# stm32devboard_f401ccu6.net
KiCad netlist of a schematic drawn in EasyEDA Pro
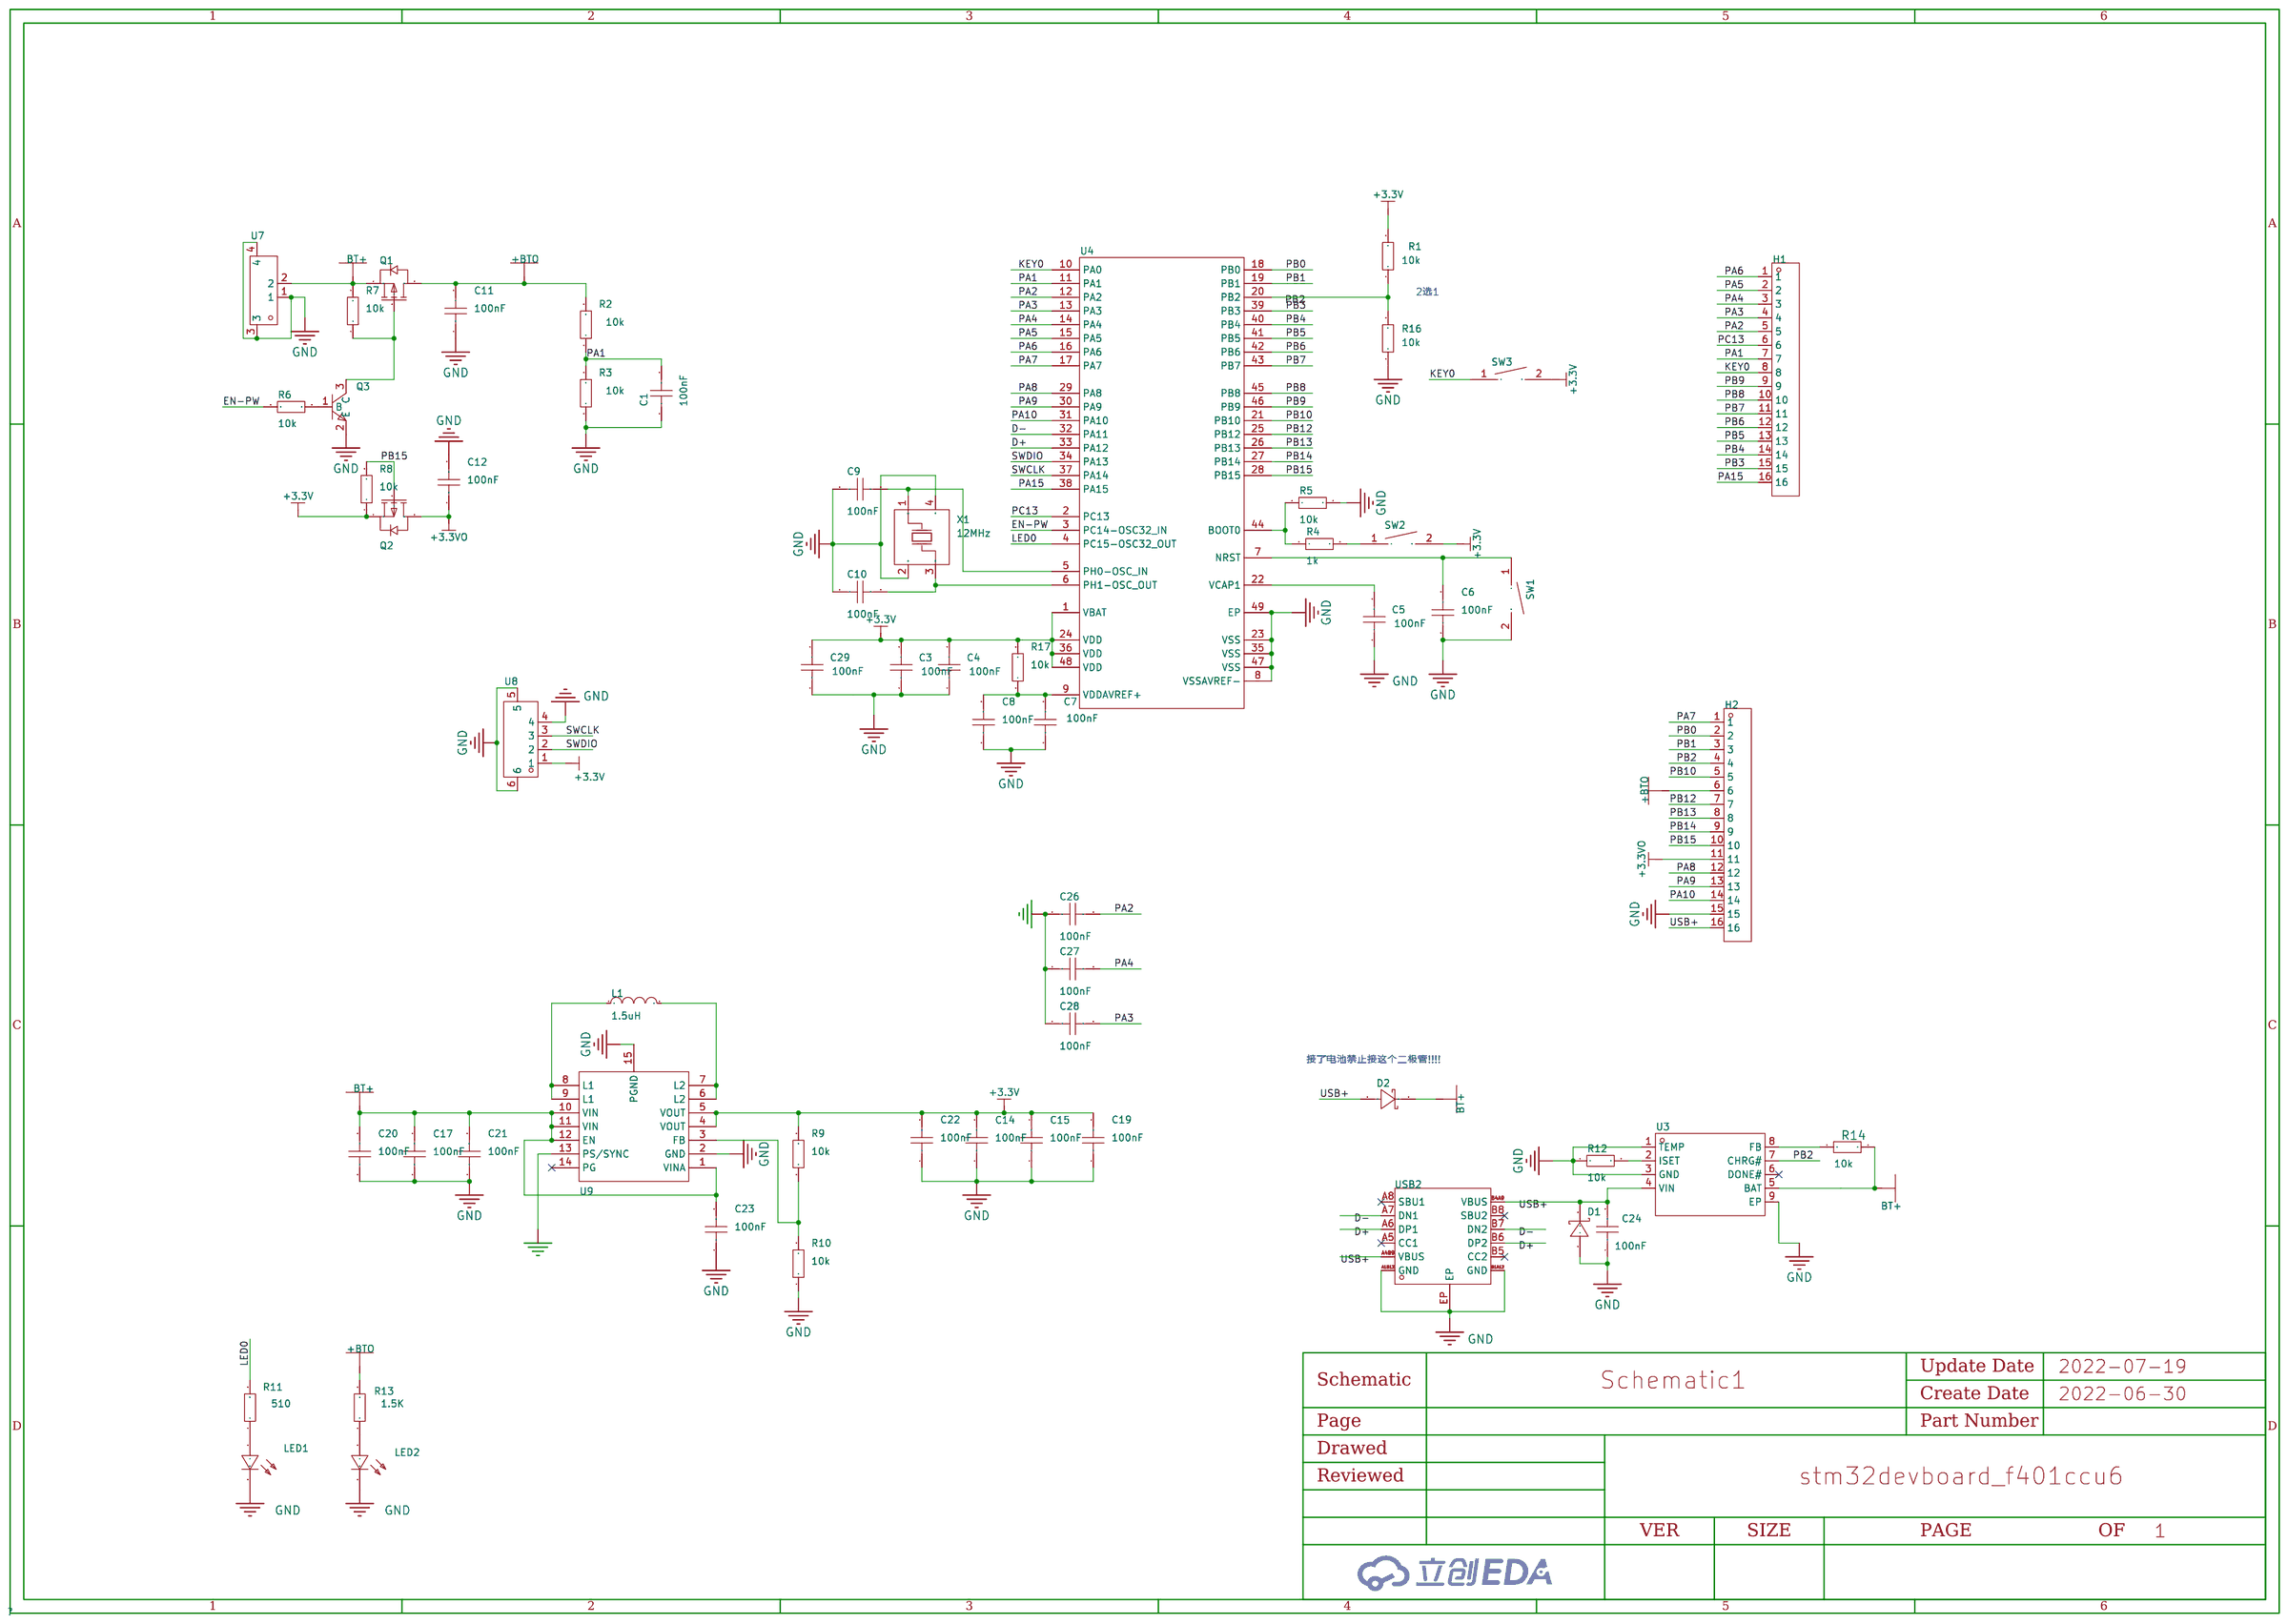
[diagram p0: schematic sheet]

(export (version "E")
  (design (tool "Eeschema 10.0.6"))
  (components
    (comp (ref "C1")
      (value "100nF")
      (footprint "easyedapro:C0402")
      (description "容值:100nF;精度:±10%;额定电压:25V;温度系数:X7R;")
      (fields (field (name "Manufacturer Part") "FN15X104K250PNG") (field (name "Manufacturer") "PSA(信昌电陶)"))
      (libsource (lib "easyedapro") (part "FN15X104K250PNG"))
    )
    (comp (ref "C3")
      (value "100nF")
      (footprint "easyedapro:C0603")
      (description "容值:100nF;精度:±10%;额定电压:50V;温度系数:X7R;")
      (fields
        (field (name "Manufacturer Part") "CC0603KRX7R9BB104")
        (field (name "Manufacturer") "YAGEO(国巨)")
      )
      (libsource (lib "easyedapro") (part "CC0603KRX7R9BB104"))
    )
    (comp (ref "C4")
      (value "100nF")
      (footprint "easyedapro:C0603")
      (description "容值:100nF;精度:±10%;额定电压:50V;温度系数:X7R;")
      (fields
        (field (name "Manufacturer Part") "CC0603KRX7R9BB104")
        (field (name "Manufacturer") "YAGEO(国巨)")
      )
      (libsource (lib "easyedapro") (part "CC0603KRX7R9BB104"))
    )
    (comp (ref "C5")
      (value "100nF")
      (footprint "easyedapro:C0603")
      (description "容值:100nF;精度:±10%;额定电压:50V;温度系数:X7R;")
      (fields
        (field (name "Manufacturer Part") "CC0603KRX7R9BB104")
        (field (name "Manufacturer") "YAGEO(国巨)")
      )
      (libsource (lib "easyedapro") (part "CC0603KRX7R9BB104"))
    )
    (comp (ref "C6")
      (value "100nF")
      (footprint "easyedapro:C0603")
      (description "容值:100nF;精度:±10%;额定电压:50V;温度系数:X7R;")
      (fields
        (field (name "Manufacturer Part") "CC0603KRX7R9BB104")
        (field (name "Manufacturer") "YAGEO(国巨)")
      )
      (libsource (lib "easyedapro") (part "CC0603KRX7R9BB104"))
    )
    (comp (ref "C7")
      (value "100nF")
      (footprint "easyedapro:C0603")
      (description "容值:100nF;精度:±10%;额定电压:50V;温度系数:X7R;")
      (fields
        (field (name "Manufacturer Part") "CC0603KRX7R9BB104")
        (field (name "Manufacturer") "YAGEO(国巨)")
      )
      (libsource (lib "easyedapro") (part "CC0603KRX7R9BB104"))
    )
    (comp (ref "C8")
      (value "100nF")
      (footprint "easyedapro:C0603")
      (description "容值:100nF;精度:±10%;额定电压:50V;温度系数:X7R;")
      (fields
        (field (name "Manufacturer Part") "CC0603KRX7R9BB104")
        (field (name "Manufacturer") "YAGEO(国巨)")
      )
      (libsource (lib "easyedapro") (part "CC0603KRX7R9BB104"))
    )
    (comp (ref "C9")
      (value "100nF")
      (footprint "easyedapro:C0603")
      (description "容值:100nF;精度:±10%;额定电压:50V;温度系数:X7R;")
      (fields
        (field (name "Manufacturer Part") "CC0603KRX7R9BB104")
        (field (name "Manufacturer") "YAGEO(国巨)")
      )
      (libsource (lib "easyedapro") (part "CC0603KRX7R9BB104"))
    )
    (comp (ref "C10")
      (value "100nF")
      (footprint "easyedapro:C0603")
      (description "容值:100nF;精度:±10%;额定电压:50V;温度系数:X7R;")
      (fields
        (field (name "Manufacturer Part") "CC0603KRX7R9BB104")
        (field (name "Manufacturer") "YAGEO(国巨)")
      )
      (libsource (lib "easyedapro") (part "CC0603KRX7R9BB104"))
    )
    (comp (ref "C11")
      (value "100nF")
      (footprint "easyedapro:C0603")
      (description "容值:100nF;精度:±10%;额定电压:50V;温度系数:X7R;")
      (fields
        (field (name "Manufacturer Part") "CC0603KRX7R9BB104")
        (field (name "Manufacturer") "YAGEO(国巨)")
      )
      (libsource (lib "easyedapro") (part "CC0603KRX7R9BB104"))
    )
    (comp (ref "C12")
      (value "100nF")
      (footprint "easyedapro:C0603")
      (description "容值:100nF;精度:±10%;额定电压:50V;温度系数:X7R;")
      (fields
        (field (name "Manufacturer Part") "CC0603KRX7R9BB104")
        (field (name "Manufacturer") "YAGEO(国巨)")
      )
      (libsource (lib "easyedapro") (part "CC0603KRX7R9BB104"))
    )
    (comp (ref "C14")
      (value "100nF")
      (footprint "easyedapro:C0603")
      (description "容值:100nF;精度:±10%;额定电压:50V;温度系数:X7R;")
      (fields
        (field (name "Manufacturer Part") "CC0603KRX7R9BB104")
        (field (name "Manufacturer") "YAGEO(国巨)")
      )
      (libsource (lib "easyedapro") (part "CC0603KRX7R9BB104"))
    )
    (comp (ref "C15")
      (value "100nF")
      (footprint "easyedapro:C0603")
      (description "容值:100nF;精度:±10%;额定电压:50V;温度系数:X7R;")
      (fields
        (field (name "Manufacturer Part") "CC0603KRX7R9BB104")
        (field (name "Manufacturer") "YAGEO(国巨)")
      )
      (libsource (lib "easyedapro") (part "CC0603KRX7R9BB104"))
    )
    (comp (ref "C17")
      (value "100nF")
      (footprint "easyedapro:C0603")
      (description "容值:100nF;精度:±10%;额定电压:50V;温度系数:X7R;")
      (fields
        (field (name "Manufacturer Part") "CC0603KRX7R9BB104")
        (field (name "Manufacturer") "YAGEO(国巨)")
      )
      (libsource (lib "easyedapro") (part "CC0603KRX7R9BB104"))
    )
    (comp (ref "C19")
      (value "100nF")
      (footprint "easyedapro:C0603")
      (description "容值:100nF;精度:±10%;额定电压:50V;温度系数:X7R;")
      (fields
        (field (name "Manufacturer Part") "CC0603KRX7R9BB104")
        (field (name "Manufacturer") "YAGEO(国巨)")
      )
      (libsource (lib "easyedapro") (part "CC0603KRX7R9BB104"))
    )
    (comp (ref "C20")
      (value "100nF")
      (footprint "easyedapro:C0603")
      (description "容值:100nF;精度:±10%;额定电压:50V;温度系数:X7R;")
      (fields
        (field (name "Manufacturer Part") "CC0603KRX7R9BB104")
        (field (name "Manufacturer") "YAGEO(国巨)")
      )
      (libsource (lib "easyedapro") (part "CC0603KRX7R9BB104"))
    )
    (comp (ref "C21")
      (value "100nF")
      (footprint "easyedapro:C0402")
      (description "容值:100nF;精度:±10%;额定电压:25V;温度系数:X7R;")
      (fields (field (name "Manufacturer Part") "FN15X104K250PNG") (field (name "Manufacturer") "PSA(信昌电陶)"))
      (libsource (lib "easyedapro") (part "FN15X104K250PNG"))
    )
    (comp (ref "C22")
      (value "100nF")
      (footprint "easyedapro:C0402")
      (description "容值:100nF;精度:±10%;额定电压:25V;温度系数:X7R;")
      (fields (field (name "Manufacturer Part") "FN15X104K250PNG") (field (name "Manufacturer") "PSA(信昌电陶)"))
      (libsource (lib "easyedapro") (part "FN15X104K250PNG"))
    )
    (comp (ref "C23")
      (value "100nF")
      (footprint "easyedapro:C0603")
      (description "容值:100nF;精度:±10%;额定电压:50V;温度系数:X7R;")
      (fields
        (field (name "Manufacturer Part") "CC0603KRX7R9BB104")
        (field (name "Manufacturer") "YAGEO(国巨)")
      )
      (libsource (lib "easyedapro") (part "CC0603KRX7R9BB104"))
    )
    (comp (ref "C24")
      (value "100nF")
      (footprint "easyedapro:C0603")
      (description "容值:100nF;精度:±10%;额定电压:50V;温度系数:X7R;")
      (fields
        (field (name "Manufacturer Part") "CC0603KRX7R9BB104")
        (field (name "Manufacturer") "YAGEO(国巨)")
      )
      (libsource (lib "easyedapro") (part "CC0603KRX7R9BB104"))
    )
    (comp (ref "C26")
      (value "100nF")
      (footprint "easyedapro:C0402")
      (description "容值:100nF;精度:±10%;额定电压:25V;温度系数:X7R;")
      (fields (field (name "Manufacturer Part") "FN15X104K250PNG") (field (name "Manufacturer") "PSA(信昌电陶)"))
      (libsource (lib "easyedapro") (part "FN15X104K250PNG"))
    )
    (comp (ref "C27")
      (value "100nF")
      (footprint "easyedapro:C0402")
      (description "容值:100nF;精度:±10%;额定电压:25V;温度系数:X7R;")
      (fields (field (name "Manufacturer Part") "FN15X104K250PNG") (field (name "Manufacturer") "PSA(信昌电陶)"))
      (libsource (lib "easyedapro") (part "FN15X104K250PNG"))
    )
    (comp (ref "C28")
      (value "100nF")
      (footprint "easyedapro:C0402")
      (description "容值:100nF;精度:±10%;额定电压:25V;温度系数:X7R;")
      (fields (field (name "Manufacturer Part") "FN15X104K250PNG") (field (name "Manufacturer") "PSA(信昌电陶)"))
      (libsource (lib "easyedapro") (part "FN15X104K250PNG"))
    )
    (comp (ref "C29")
      (value "100nF")
      (footprint "easyedapro:C0402")
      (description "容值:100nF;精度:±10%;额定电压:25V;温度系数:X7R;")
      (fields (field (name "Manufacturer Part") "FN15X104K250PNG") (field (name "Manufacturer") "PSA(信昌电陶)"))
      (libsource (lib "easyedapro") (part "FN15X104K250PNG"))
    )
    (comp (ref "D1")
      (value "~")
      (footprint "easyedapro:SOD-123FL_L2.6-W1.6-LS3.4-R-FD")
      (description "极性:单向;反向截止电压(Vrwm):5V;击穿电压(最小值):6.4V;峰值脉冲电流(Ipp)@10/1000s:21.7A;最大钳位电压:9.4V;")
      (fields (field (name "Manufacturer Part") "SMFJ5.0A") (field (name "Manufacturer") "BORN伯恩半导体"))
      (libsource (lib "easyedapro") (part "SMFJ5.0A_C151893"))
    )
    (comp (ref "D2")
      (value "~")
      (footprint "easyedapro:SOD-323_L1.6-W1.3-LS2.7-RD")
      (description "二极管配置:独立式;直流反向耐压(Vr):40V;平均整流电流(Io):350mA;正向压降(Vf):600mV@200mA;反向电流(Ir):5A@30V;")
      (fields (field (name "Manufacturer Part") "1N5819WS S4") (field (name "Manufacturer") "JSMSEMI(杰盛微)"))
      (libsource (lib "easyedapro") (part "1N5819WS S4"))
    )
    (comp (ref "H1")
      (value "~")
      (footprint "easyedapro:HDR-TH_16P-P2.54-V-M")
      (description "2.54mm 圆孔排针,单排,180度,塑高3.0mm,塑宽2.54mm,D4.3mm,L=12.20mm,PPS料,镀金,16P")
      (fields
        (field (name "Manufacturer Part") "X5511WV-16-C396D43-1220")
        (field (name "Manufacturer") "XKB Connectivity(中国星坤)")
      )
      (libsource (lib "easyedapro") (part "X5511WV-16-C396D43-1220"))
    )
    (comp (ref "H2")
      (value "~")
      (footprint "easyedapro:HDR-TH_16P-P2.54-V-M")
      (description "2.54mm 圆孔排针,单排,180度,塑高3.0mm,塑宽2.54mm,D4.3mm,L=12.20mm,PPS料,镀金,16P")
      (fields
        (field (name "Manufacturer Part") "X5511WV-16-C396D43-1220")
        (field (name "Manufacturer") "XKB Connectivity(中国星坤)")
      )
      (libsource (lib "easyedapro") (part "X5511WV-16-C396D43-1220"))
    )
    (comp (ref "L1")
      (value "1.5uH")
      (footprint "easyedapro:IND-SMD_L4.0-W4.0_FNR40XXS")
      (description "电感值:1.5uH;精度:±20%;额定电流:3.34A;直流电阻(DCR):26m;")
      (fields (field (name "Manufacturer Part") "FNR4030S1R5MT") (field (name "Manufacturer") "cjiang(长江微电)"))
      (libsource (lib "easyedapro") (part "FNR4030S1R5MT"))
    )
    (comp (ref "LED1")
      (value "~")
      (footprint "easyedapro:LED0603-R-RD")
      (description "照明颜色:翠绿;色温 - CCT（K）:-;主波长/色坐标:520~535nm;")
      (fields
        (field (name "Manufacturer Part") "19-217/GHC-YR1S2/3T")
        (field (name "Manufacturer") "EVERLIGHT(台湾亿光)")
      )
      (libsource (lib "easyedapro") (part "19-217/GHC-YR1S2/3T"))
    )
    (comp (ref "LED2")
      (value "~")
      (footprint "easyedapro:LED0603-R-RD")
      (description "照明颜色:翠绿;色温 - CCT（K）:-;主波长/色坐标:520~535nm;")
      (fields
        (field (name "Manufacturer Part") "19-217/GHC-YR1S2/3T")
        (field (name "Manufacturer") "EVERLIGHT(台湾亿光)")
      )
      (libsource (lib "easyedapro") (part "19-217/GHC-YR1S2/3T"))
    )
    (comp (ref "Q1")
      (value "~")
      (footprint "easyedapro:SOT-23-3_L2.9-W1.3-P1.90-LS2.4-TR")
      (fields (field (name "Manufacturer Part") "AP2301B") (field (name "Manufacturer") "ALLPOWER(铨力)"))
      (libsource (lib "easyedapro") (part "AP2301B"))
    )
    (comp (ref "Q2")
      (value "~")
      (footprint "easyedapro:SOT-23-3_L2.9-W1.3-P1.90-LS2.4-TR")
      (fields (field (name "Manufacturer Part") "AP2301B") (field (name "Manufacturer") "ALLPOWER(铨力)"))
      (libsource (lib "easyedapro") (part "AP2301B"))
    )
    (comp (ref "Q3")
      (value "~")
      (footprint "easyedapro:SOT-23-3_L2.9-W1.3-P1.90-LS2.4-BR")
      (fields (field (name "Manufacturer Part") "S8050 J3Y") (field (name "Manufacturer") "FOSAN(富信)"))
      (libsource (lib "easyedapro") (part "S8050_C2926165"))
    )
    (comp (ref "R1")
      (value "10k")
      (footprint "easyedapro:R0603")
      (description "电阻类型:薄膜电阻;阻值:10k;精度:±0.1%;功率:100mW;温度系数:±25ppm/;最大工作电压:75V;工作温度范围:-55~+155;")
      (fields
        (field (name "Manufacturer Part") "TR0603B10K0P0525Z")
        (field (name "Manufacturer") "EVER OHMS(天二科技)")
      )
      (libsource (lib "easyedapro") (part "R_0603_EU"))
    )
    (comp (ref "R2")
      (value "10k")
      (footprint "easyedapro:R0603")
      (description "电阻类型:薄膜电阻;阻值:10k;精度:±0.1%;功率:100mW;温度系数:±25ppm/;最大工作电压:75V;工作温度范围:-55~+155;")
      (fields
        (field (name "Manufacturer Part") "TR0603B10K0P0525Z")
        (field (name "Manufacturer") "EVER OHMS(天二科技)")
      )
      (libsource (lib "easyedapro") (part "R_0603_EU"))
    )
    (comp (ref "R3")
      (value "10k")
      (footprint "easyedapro:R0603")
      (description "电阻类型:薄膜电阻;阻值:10k;精度:±0.1%;功率:100mW;温度系数:±25ppm/;最大工作电压:75V;工作温度范围:-55~+155;")
      (fields
        (field (name "Manufacturer Part") "TR0603B10K0P0525Z")
        (field (name "Manufacturer") "EVER OHMS(天二科技)")
      )
      (libsource (lib "easyedapro") (part "R_0603_EU"))
    )
    (comp (ref "R4")
      (value "1k")
      (footprint "easyedapro:R0603")
      (description "电阻类型:薄膜电阻;阻值:10k;精度:±0.1%;功率:100mW;温度系数:±25ppm/;最大工作电压:75V;工作温度范围:-55~+155;")
      (fields
        (field (name "Manufacturer Part") "TR0603B10K0P0525Z")
        (field (name "Manufacturer") "EVER OHMS(天二科技)")
      )
      (libsource (lib "easyedapro") (part "R_0603_EU"))
    )
    (comp (ref "R5")
      (value "10k")
      (footprint "easyedapro:R0603")
      (description "电阻类型:薄膜电阻;阻值:10k;精度:±0.1%;功率:100mW;温度系数:±25ppm/;最大工作电压:75V;工作温度范围:-55~+155;")
      (fields
        (field (name "Manufacturer Part") "TR0603B10K0P0525Z")
        (field (name "Manufacturer") "EVER OHMS(天二科技)")
      )
      (libsource (lib "easyedapro") (part "R_0603_EU"))
    )
    (comp (ref "R6")
      (value "10k")
      (footprint "easyedapro:R0603")
      (description "电阻类型:薄膜电阻;阻值:10k;精度:±0.1%;功率:100mW;温度系数:±25ppm/;最大工作电压:75V;工作温度范围:-55~+155;")
      (fields
        (field (name "Manufacturer Part") "TR0603B10K0P0525Z")
        (field (name "Manufacturer") "EVER OHMS(天二科技)")
      )
      (libsource (lib "easyedapro") (part "R_0603_EU"))
    )
    (comp (ref "R7")
      (value "10k")
      (footprint "easyedapro:R0603")
      (description "电阻类型:薄膜电阻;阻值:10k;精度:±0.1%;功率:100mW;温度系数:±25ppm/;最大工作电压:75V;工作温度范围:-55~+155;")
      (fields
        (field (name "Manufacturer Part") "TR0603B10K0P0525Z")
        (field (name "Manufacturer") "EVER OHMS(天二科技)")
      )
      (libsource (lib "easyedapro") (part "R_0603_EU"))
    )
    (comp (ref "R8")
      (value "10k")
      (footprint "easyedapro:R0603")
      (description "电阻类型:薄膜电阻;阻值:10k;精度:±0.1%;功率:100mW;温度系数:±25ppm/;最大工作电压:75V;工作温度范围:-55~+155;")
      (fields
        (field (name "Manufacturer Part") "TR0603B10K0P0525Z")
        (field (name "Manufacturer") "EVER OHMS(天二科技)")
      )
      (libsource (lib "easyedapro") (part "R_0603_EU"))
    )
    (comp (ref "R9")
      (value "10k")
      (footprint "easyedapro:R0603")
      (description "电阻类型:薄膜电阻;阻值:10k;精度:±0.1%;功率:100mW;温度系数:±25ppm/;最大工作电压:75V;工作温度范围:-55~+155;")
      (fields
        (field (name "Manufacturer Part") "TR0603B10K0P0525Z")
        (field (name "Manufacturer") "EVER OHMS(天二科技)")
      )
      (libsource (lib "easyedapro") (part "R_0603_EU"))
    )
    (comp (ref "R10")
      (value "10k")
      (footprint "easyedapro:R0603")
      (description "电阻类型:薄膜电阻;阻值:10k;精度:±0.1%;功率:100mW;温度系数:±25ppm/;最大工作电压:75V;工作温度范围:-55~+155;")
      (fields
        (field (name "Manufacturer Part") "TR0603B10K0P0525Z")
        (field (name "Manufacturer") "EVER OHMS(天二科技)")
      )
      (libsource (lib "easyedapro") (part "R_0603_EU"))
    )
    (comp (ref "R11")
      (value "510")
      (footprint "easyedapro:R0603")
      (description "电阻类型:薄膜电阻;阻值:10k;精度:±0.1%;功率:100mW;温度系数:±25ppm/;最大工作电压:75V;工作温度范围:-55~+155;")
      (fields
        (field (name "Manufacturer Part") "TR0603B10K0P0525Z")
        (field (name "Manufacturer") "EVER OHMS(天二科技)")
      )
      (libsource (lib "easyedapro") (part "R_0603_EU"))
    )
    (comp (ref "R12")
      (value "10k")
      (footprint "easyedapro:R0603")
      (description "电阻类型:薄膜电阻;阻值:10k;精度:±0.1%;功率:100mW;温度系数:±25ppm/;最大工作电压:75V;工作温度范围:-55~+155;")
      (fields
        (field (name "Manufacturer Part") "TR0603B10K0P0525Z")
        (field (name "Manufacturer") "EVER OHMS(天二科技)")
      )
      (libsource (lib "easyedapro") (part "R_0603_EU"))
    )
    (comp (ref "R13")
      (value "1.5K")
      (footprint "easyedapro:R0603")
      (description "电阻类型:薄膜电阻;阻值:10k;精度:±0.1%;功率:100mW;温度系数:±25ppm/;最大工作电压:75V;工作温度范围:-55~+155;")
      (fields
        (field (name "Manufacturer Part") "TR0603B10K0P0525Z")
        (field (name "Manufacturer") "EVER OHMS(天二科技)")
      )
      (libsource (lib "easyedapro") (part "R_0603_EU"))
    )
    (comp (ref "R14")
      (value "10k")
      (footprint "easyedapro:R0603_1")
      (description "阻值:10k;精度:±0.1%;温度系数:±25ppm/;功率:100mW;工作温度范围:-55~+155;电阻类型:薄膜电阻;最大工作电压:75V;")
      (fields
        (field (name "Manufacturer Part") "TR0603B10K0P0525Z")
        (field (name "Manufacturer") "EVER OHMS(天二科技)")
      )
      (libsource (lib "easyedapro") (part "TR0603B10KP05250.1W"))
    )
    (comp (ref "R16")
      (value "10k")
      (footprint "easyedapro:R0603")
      (description "电阻类型:薄膜电阻;阻值:10k;精度:±0.1%;功率:100mW;温度系数:±25ppm/;最大工作电压:75V;工作温度范围:-55~+155;")
      (fields
        (field (name "Manufacturer Part") "TR0603B10K0P0525Z")
        (field (name "Manufacturer") "EVER OHMS(天二科技)")
      )
      (libsource (lib "easyedapro") (part "R_0603_EU"))
    )
    (comp (ref "R17")
      (value "10k")
      (footprint "easyedapro:R0603")
      (description "电阻类型:薄膜电阻;阻值:10k;精度:±0.1%;功率:100mW;温度系数:±25ppm/;最大工作电压:75V;工作温度范围:-55~+155;")
      (fields
        (field (name "Manufacturer Part") "TR0603B10K0P0525Z")
        (field (name "Manufacturer") "EVER OHMS(天二科技)")
      )
      (libsource (lib "easyedapro") (part "R_0603_EU"))
    )
    (comp (ref "SW1")
      (value "~")
      (footprint "easyedapro:SW-SMD_L4.0-W2.9-LS5.0")
      (fields
        (field (name "Manufacturer Part") "TSA343G00-250J2")
        (field (name "Manufacturer") "BRIGHT(博瑞泰)")
      )
      (libsource (lib "easyedapro") (part "TSA343G00-250J2"))
    )
    (comp (ref "SW2")
      (value "~")
      (footprint "easyedapro:SW-SMD_L4.0-W2.9-LS5.0")
      (fields
        (field (name "Manufacturer Part") "TSA343G00-250J2")
        (field (name "Manufacturer") "BRIGHT(博瑞泰)")
      )
      (libsource (lib "easyedapro") (part "TSA343G00-250J2"))
    )
    (comp (ref "SW3")
      (value "~")
      (footprint "easyedapro:SW-SMD_L4.0-W2.9-LS5.0")
      (fields
        (field (name "Manufacturer Part") "TSA343G00-250J2")
        (field (name "Manufacturer") "BRIGHT(博瑞泰)")
      )
      (libsource (lib "easyedapro") (part "TSA343G00-250J2"))
    )
    (comp (ref "U3")
      (value "~")
      (footprint "easyedapro:SOP-8_L4.9-W3.9-P1.27-LS6.0-BL-EP")
      (description "充电电池的类型:-;电池单元组数:-;最大充电电流:-;充满的电池组电压:-;最大供应电压:-;")
      (fields (field (name "Manufacturer Part") "CN3058E") (field (name "Manufacturer") "CONSONANCE(上海如韵)"))
      (libsource (lib "easyedapro") (part "CN3058E"))
    )
    (comp (ref "U4")
      (value "~")
      (footprint "easyedapro:UFQFPN-48_L7.0-W7.0-P0.50-BL-EP")
      (description "主频（MAX):84MHz;工作电压:1.7V ~ 3.6V;")
      (fields (field (name "Manufacturer Part") "STM32F401CEU6") (field (name "Manufacturer") "ST(意法半导体)"))
      (libsource (lib "easyedapro") (part "STM32F401CEU6"))
    )
    (comp (ref "U7")
      (value "~")
      (footprint "easyedapro:CONN-SMD_2P-P1.25_GH1.25-2P")
      (fields
        (field (name "Manufacturer Part") "GH1.25-2PLTPZ")
        (field (name "Manufacturer") "BOOMELE(博穆精密)")
      )
      (libsource (lib "easyedapro") (part "GH1.25-2PLTPZ"))
    )
    (comp (ref "U8")
      (value "~")
      (footprint "easyedapro:CONN-TH_4P-P1.25_XUNPU_WAFER-GH1.25-4PLB")
      (fields
        (field (name "Manufacturer Part") "WAFER-GH1.25-4PLB")
        (field (name "Manufacturer") "XUNPU(讯普)")
      )
      (libsource (lib "easyedapro") (part "WAFER-GH1.25-4PLB"))
    )
    (comp (ref "U9")
      (value "~")
      (footprint "easyedapro:VSON-14_L4.0-W3.0-P0.50-BL-EP_TI_DSJ")
      (description "功能类型:升降压型;同步整流:是;输出通道数:1;拓扑结构:降压-升压式;输入电压:1.8V~5.5V;输出电压:1.2V~5.5V;输出电流(最大值):3.5A;开关频率:2.4MHz;")
      (fields (field (name "Manufacturer Part") "TPS63020DSJR") (field (name "Manufacturer") "TI(德州仪器)"))
      (libsource (lib "easyedapro") (part "TPS63020DSJR"))
    )
    (comp (ref "USB2")
      (value "~")
      (footprint "easyedapro:USB-C-SMD_TYPE-C-16P-1")
      (description "连接器类型:Type-C;公母:母座;触点数量:16;端口数量:1;安装方式:卧贴;额定电流 - 电源:3A;工作温度范围:-40~+85;")
      (fields (field (name "Manufacturer Part") "TYPEC-304-ACP16") (field (name "Manufacturer") "XUNPU(讯普)"))
      (libsource (lib "easyedapro") (part "TYPEC-304-ACP16"))
    )
    (comp (ref "X1")
      (value "12MHz")
      (footprint "easyedapro:OSC-SMD_4P-L3.2-W2.5-BL")
      (description "晶振类型:贴片无源晶振;频率:12MHz;频率公差:±10ppm;频率稳定度:±30ppm;负载电容:20pF;工作温度:-40~+85;")
      (fields (field (name "Manufacturer Part") "X322512MSB4SI") (field (name "Manufacturer") "YXC扬兴科技"))
      (libsource (lib "easyedapro") (part "X322512MSB4SI"))
    )
  )
  (nets
    (net (code "1") (name "+3.3V") (class "Default")
      (node (ref "C14") (pin "2") (pinfunction "2_2") (pintype "input"))
      (node (ref "C15") (pin "2") (pinfunction "2_2") (pintype "input"))
      (node (ref "C19") (pin "2") (pinfunction "2_2") (pintype "input"))
      (node (ref "C22") (pin "2") (pinfunction "2_2") (pintype "input"))
      (node (ref "C29") (pin "2") (pinfunction "2_2") (pintype "input"))
      (node (ref "C3") (pin "2") (pinfunction "2_2") (pintype "input"))
      (node (ref "C4") (pin "2") (pinfunction "2_2") (pintype "input"))
      (node (ref "Q2") (pin "1") (pinfunction "S_1") (pintype "input"))
      (node (ref "R1") (pin "2") (pinfunction "2_2") (pintype "input"))
      (node (ref "R17") (pin "2") (pinfunction "2_2") (pintype "input"))
      (node (ref "R8") (pin "1") (pinfunction "1_1") (pintype "input"))
      (node (ref "R9") (pin "2") (pinfunction "2_2") (pintype "input"))
      (node (ref "SW2") (pin "2") (pinfunction "2_2") (pintype "input"))
      (node (ref "SW3") (pin "2") (pinfunction "2_2") (pintype "input"))
      (node (ref "U4") (pin "1") (pinfunction "VBAT_1") (pintype "input"))
      (node (ref "U4") (pin "24") (pinfunction "VDD_24") (pintype "input"))
      (node (ref "U4") (pin "36") (pinfunction "VDD_36") (pintype "input"))
      (node (ref "U4") (pin "48") (pinfunction "VDD_48") (pintype "input"))
      (node (ref "U8") (pin "1") (pinfunction "1_1") (pintype "input"))
      (node (ref "U9") (pin "4") (pinfunction "VOUT_4") (pintype "input"))
      (node (ref "U9") (pin "5") (pinfunction "VOUT_5") (pintype "input"))
    )
    (net (code "2") (name "+3.3VO") (class "Default")
      (node (ref "C12") (pin "1") (pinfunction "1_1") (pintype "input"))
      (node (ref "H2") (pin "11") (pinfunction "11_11") (pintype "input"))
      (node (ref "Q2") (pin "3") (pinfunction "D_3") (pintype "input"))
    )
    (net (code "3") (name "+BTO") (class "Default")
      (node (ref "C11") (pin "2") (pinfunction "2_2") (pintype "input"))
      (node (ref "H2") (pin "6") (pinfunction "6_6") (pintype "input"))
      (node (ref "Q1") (pin "3") (pinfunction "D_3") (pintype "input"))
      (node (ref "R13") (pin "2") (pinfunction "2_2") (pintype "input"))
      (node (ref "R2") (pin "2") (pinfunction "2_2") (pintype "input"))
    )
    (net (code "4") (name "/D+") (class "Default")
      (node (ref "U4") (pin "33") (pinfunction "PA12_33") (pintype "bidirectional"))
      (node (ref "USB2") (pin "A6") (pinfunction "DP1_A6") (pintype "input"))
      (node (ref "USB2") (pin "B6") (pinfunction "DP2_B6") (pintype "input"))
    )
    (net (code "5") (name "/D-") (class "Default")
      (node (ref "U4") (pin "32") (pinfunction "PA11_32") (pintype "bidirectional"))
      (node (ref "USB2") (pin "A7") (pinfunction "DN1_A7") (pintype "input"))
      (node (ref "USB2") (pin "B7") (pinfunction "DN2_B7") (pintype "input"))
    )
    (net (code "6") (name "/EN-PW") (class "Default")
      (node (ref "R6") (pin "1") (pinfunction "1_1") (pintype "input"))
      (node (ref "U4") (pin "3") (pinfunction "PC14-OSC32_IN_3") (pintype "bidirectional"))
    )
    (net (code "7") (name "/KEY0") (class "Default")
      (node (ref "H1") (pin "8") (pinfunction "8_8") (pintype "input"))
      (node (ref "SW3") (pin "1") (pinfunction "1_1") (pintype "input"))
      (node (ref "U4") (pin "10") (pinfunction "PA0_10") (pintype "bidirectional"))
    )
    (net (code "8") (name "/LED0") (class "Default")
      (node (ref "R11") (pin "2") (pinfunction "2_2") (pintype "input"))
      (node (ref "U4") (pin "4") (pinfunction "PC15-OSC32_OUT_4") (pintype "bidirectional"))
    )
    (net (code "9") (name "/PA1") (class "Default")
      (node (ref "C1") (pin "2") (pinfunction "2_2") (pintype "input"))
      (node (ref "H1") (pin "7") (pinfunction "7_7") (pintype "input"))
      (node (ref "R2") (pin "1") (pinfunction "1_1") (pintype "input"))
      (node (ref "R3") (pin "2") (pinfunction "2_2") (pintype "input"))
      (node (ref "U4") (pin "11") (pinfunction "PA1_11") (pintype "bidirectional"))
    )
    (net (code "10") (name "/PA2") (class "Default")
      (node (ref "C26") (pin "2") (pinfunction "2_2") (pintype "input"))
      (node (ref "H1") (pin "5") (pinfunction "5_5") (pintype "input"))
      (node (ref "U4") (pin "12") (pinfunction "PA2_12") (pintype "bidirectional"))
    )
    (net (code "11") (name "/PA3") (class "Default")
      (node (ref "C28") (pin "2") (pinfunction "2_2") (pintype "input"))
      (node (ref "H1") (pin "4") (pinfunction "4_4") (pintype "input"))
      (node (ref "U4") (pin "13") (pinfunction "PA3_13") (pintype "bidirectional"))
    )
    (net (code "12") (name "/PA4") (class "Default")
      (node (ref "C27") (pin "2") (pinfunction "2_2") (pintype "input"))
      (node (ref "H1") (pin "3") (pinfunction "3_3") (pintype "input"))
      (node (ref "U4") (pin "14") (pinfunction "PA4_14") (pintype "bidirectional"))
    )
    (net (code "13") (name "/PA5") (class "Default")
      (node (ref "H1") (pin "2") (pinfunction "2_2") (pintype "input"))
      (node (ref "U4") (pin "15") (pinfunction "PA5_15") (pintype "bidirectional"))
    )
    (net (code "14") (name "/PA6") (class "Default")
      (node (ref "H1") (pin "1") (pinfunction "1_1") (pintype "input"))
      (node (ref "U4") (pin "16") (pinfunction "PA6_16") (pintype "bidirectional"))
    )
    (net (code "15") (name "/PA7") (class "Default")
      (node (ref "H2") (pin "1") (pinfunction "1_1") (pintype "input"))
      (node (ref "U4") (pin "17") (pinfunction "PA7_17") (pintype "bidirectional"))
    )
    (net (code "16") (name "/PA8") (class "Default")
      (node (ref "H2") (pin "12") (pinfunction "12_12") (pintype "input"))
      (node (ref "U4") (pin "29") (pinfunction "PA8_29") (pintype "bidirectional"))
    )
    (net (code "17") (name "/PA9") (class "Default")
      (node (ref "H2") (pin "13") (pinfunction "13_13") (pintype "input"))
      (node (ref "U4") (pin "30") (pinfunction "PA9_30") (pintype "bidirectional"))
    )
    (net (code "18") (name "/PA10") (class "Default")
      (node (ref "H2") (pin "14") (pinfunction "14_14") (pintype "input"))
      (node (ref "U4") (pin "31") (pinfunction "PA10_31") (pintype "bidirectional"))
    )
    (net (code "19") (name "/PA15") (class "Default")
      (node (ref "H1") (pin "16") (pinfunction "16_16") (pintype "input"))
      (node (ref "U4") (pin "38") (pinfunction "PA15_38") (pintype "bidirectional"))
    )
    (net (code "20") (name "/PB0") (class "Default")
      (node (ref "H2") (pin "2") (pinfunction "2_2") (pintype "input"))
      (node (ref "U4") (pin "18") (pinfunction "PB0_18") (pintype "bidirectional"))
    )
    (net (code "21") (name "/PB1") (class "Default")
      (node (ref "H2") (pin "3") (pinfunction "3_3") (pintype "input"))
      (node (ref "U4") (pin "19") (pinfunction "PB1_19") (pintype "bidirectional"))
    )
    (net (code "22") (name "/PB2") (class "Default")
      (node (ref "H2") (pin "4") (pinfunction "4_4") (pintype "input"))
      (node (ref "R1") (pin "1") (pinfunction "1_1") (pintype "input"))
      (node (ref "R16") (pin "2") (pinfunction "2_2") (pintype "input"))
      (node (ref "U3") (pin "7") (pinfunction "CHRG#_7") (pintype "input"))
      (node (ref "U4") (pin "20") (pinfunction "PB2_20") (pintype "bidirectional"))
    )
    (net (code "23") (name "/PB3") (class "Default")
      (node (ref "H1") (pin "15") (pinfunction "15_15") (pintype "input"))
      (node (ref "U4") (pin "39") (pinfunction "PB3_39") (pintype "bidirectional"))
    )
    (net (code "24") (name "/PB4") (class "Default")
      (node (ref "H1") (pin "14") (pinfunction "14_14") (pintype "input"))
      (node (ref "U4") (pin "40") (pinfunction "PB4_40") (pintype "bidirectional"))
    )
    (net (code "25") (name "/PB5") (class "Default")
      (node (ref "H1") (pin "13") (pinfunction "13_13") (pintype "input"))
      (node (ref "U4") (pin "41") (pinfunction "PB5_41") (pintype "bidirectional"))
    )
    (net (code "26") (name "/PB6") (class "Default")
      (node (ref "H1") (pin "12") (pinfunction "12_12") (pintype "input"))
      (node (ref "U4") (pin "42") (pinfunction "PB6_42") (pintype "bidirectional"))
    )
    (net (code "27") (name "/PB7") (class "Default")
      (node (ref "H1") (pin "11") (pinfunction "11_11") (pintype "input"))
      (node (ref "U4") (pin "43") (pinfunction "PB7_43") (pintype "bidirectional"))
    )
    (net (code "28") (name "/PB8") (class "Default")
      (node (ref "H1") (pin "10") (pinfunction "10_10") (pintype "input"))
      (node (ref "U4") (pin "45") (pinfunction "PB8_45") (pintype "bidirectional"))
    )
    (net (code "29") (name "/PB9") (class "Default")
      (node (ref "H1") (pin "9") (pinfunction "9_9") (pintype "input"))
      (node (ref "U4") (pin "46") (pinfunction "PB9_46") (pintype "bidirectional"))
    )
    (net (code "30") (name "/PB10") (class "Default")
      (node (ref "H2") (pin "5") (pinfunction "5_5") (pintype "input"))
      (node (ref "U4") (pin "21") (pinfunction "PB10_21") (pintype "bidirectional"))
    )
    (net (code "31") (name "/PB12") (class "Default")
      (node (ref "H2") (pin "7") (pinfunction "7_7") (pintype "input"))
      (node (ref "U4") (pin "25") (pinfunction "PB12_25") (pintype "bidirectional"))
    )
    (net (code "32") (name "/PB13") (class "Default")
      (node (ref "H2") (pin "8") (pinfunction "8_8") (pintype "input"))
      (node (ref "U4") (pin "26") (pinfunction "PB13_26") (pintype "bidirectional"))
    )
    (net (code "33") (name "/PB14") (class "Default")
      (node (ref "H2") (pin "9") (pinfunction "9_9") (pintype "input"))
      (node (ref "U4") (pin "27") (pinfunction "PB14_27") (pintype "bidirectional"))
    )
    (net (code "34") (name "/PB15") (class "Default")
      (node (ref "H2") (pin "10") (pinfunction "10_10") (pintype "input"))
      (node (ref "Q2") (pin "2") (pinfunction "G_2") (pintype "input"))
      (node (ref "R8") (pin "2") (pinfunction "2_2") (pintype "input"))
      (node (ref "U4") (pin "28") (pinfunction "PB15_28") (pintype "bidirectional"))
    )
    (net (code "35") (name "/PC13") (class "Default")
      (node (ref "H1") (pin "6") (pinfunction "6_6") (pintype "input"))
      (node (ref "U4") (pin "2") (pinfunction "PC13_2") (pintype "bidirectional"))
    )
    (net (code "36") (name "/SWCLK") (class "Default")
      (node (ref "U4") (pin "37") (pinfunction "PA14_37") (pintype "bidirectional"))
      (node (ref "U8") (pin "3") (pinfunction "3_3") (pintype "input"))
    )
    (net (code "37") (name "/SWDIO") (class "Default")
      (node (ref "U4") (pin "34") (pinfunction "PA13_34") (pintype "bidirectional"))
      (node (ref "U8") (pin "2") (pinfunction "2_2") (pintype "input"))
    )
    (net (code "38") (name "/USB+") (class "Default")
      (node (ref "C24") (pin "2") (pinfunction "2_2") (pintype "input"))
      (node (ref "D1") (pin "1") (pinfunction "K_1") (pintype "input"))
      (node (ref "D2") (pin "2") (pinfunction "A_2") (pintype "input"))
      (node (ref "H2") (pin "16") (pinfunction "16_16") (pintype "input"))
      (node (ref "U3") (pin "4") (pinfunction "VIN_4") (pintype "input"))
      (node (ref "USB2") (pin "A4B9") (pinfunction "VBUS_A4B9") (pintype "input"))
      (node (ref "USB2") (pin "B4A9") (pinfunction "VBUS_B4A9") (pintype "input"))
    )
    (net (code "39") (name "BT+") (class "Default")
      (node (ref "C17") (pin "2") (pinfunction "2_2") (pintype "input"))
      (node (ref "C20") (pin "2") (pinfunction "2_2") (pintype "input"))
      (node (ref "C21") (pin "2") (pinfunction "2_2") (pintype "input"))
      (node (ref "C23") (pin "2") (pinfunction "2_2") (pintype "input"))
      (node (ref "D2") (pin "1") (pinfunction "C_1") (pintype "input"))
      (node (ref "Q1") (pin "1") (pinfunction "S_1") (pintype "input"))
      (node (ref "R14") (pin "2") (pinfunction "2_2") (pintype "unspecified"))
      (node (ref "R7") (pin "2") (pinfunction "2_2") (pintype "input"))
      (node (ref "U3") (pin "5") (pinfunction "BAT_5") (pintype "input"))
      (node (ref "U7") (pin "2") (pinfunction "2_2") (pintype "input"))
      (node (ref "U9") (pin "1") (pinfunction "VINA_1") (pintype "input"))
      (node (ref "U9") (pin "10") (pinfunction "VIN_10") (pintype "input"))
      (node (ref "U9") (pin "11") (pinfunction "VIN_11") (pintype "input"))
      (node (ref "U9") (pin "12") (pinfunction "EN_12") (pintype "input"))
    )
    (net (code "40") (name "GND") (class "Default")
      (node (ref "C1") (pin "1") (pinfunction "1_1") (pintype "input"))
      (node (ref "C10") (pin "1") (pinfunction "1_1") (pintype "input"))
      (node (ref "C11") (pin "1") (pinfunction "1_1") (pintype "input"))
      (node (ref "C12") (pin "2") (pinfunction "2_2") (pintype "input"))
      (node (ref "C14") (pin "1") (pinfunction "1_1") (pintype "input"))
      (node (ref "C15") (pin "1") (pinfunction "1_1") (pintype "input"))
      (node (ref "C17") (pin "1") (pinfunction "1_1") (pintype "input"))
      (node (ref "C19") (pin "1") (pinfunction "1_1") (pintype "input"))
      (node (ref "C20") (pin "1") (pinfunction "1_1") (pintype "input"))
      (node (ref "C21") (pin "1") (pinfunction "1_1") (pintype "input"))
      (node (ref "C22") (pin "1") (pinfunction "1_1") (pintype "input"))
      (node (ref "C23") (pin "1") (pinfunction "1_1") (pintype "input"))
      (node (ref "C24") (pin "1") (pinfunction "1_1") (pintype "input"))
      (node (ref "C26") (pin "1") (pinfunction "1_1") (pintype "input"))
      (node (ref "C27") (pin "1") (pinfunction "1_1") (pintype "input"))
      (node (ref "C28") (pin "1") (pinfunction "1_1") (pintype "input"))
      (node (ref "C29") (pin "1") (pinfunction "1_1") (pintype "input"))
      (node (ref "C3") (pin "1") (pinfunction "1_1") (pintype "input"))
      (node (ref "C4") (pin "1") (pinfunction "1_1") (pintype "input"))
      (node (ref "C5") (pin "1") (pinfunction "1_1") (pintype "input"))
      (node (ref "C6") (pin "1") (pinfunction "1_1") (pintype "input"))
      (node (ref "C7") (pin "1") (pinfunction "1_1") (pintype "input"))
      (node (ref "C8") (pin "1") (pinfunction "1_1") (pintype "input"))
      (node (ref "C9") (pin "1") (pinfunction "1_1") (pintype "input"))
      (node (ref "D1") (pin "2") (pinfunction "A_2") (pintype "input"))
      (node (ref "H2") (pin "15") (pinfunction "15_15") (pintype "input"))
      (node (ref "LED1") (pin "2") (pinfunction "C_2") (pintype "input"))
      (node (ref "LED2") (pin "2") (pinfunction "C_2") (pintype "input"))
      (node (ref "Q3") (pin "2") (pinfunction "E_2") (pintype "input"))
      (node (ref "R10") (pin "1") (pinfunction "1_1") (pintype "input"))
      (node (ref "R12") (pin "1") (pinfunction "1_1") (pintype "input"))
      (node (ref "R16") (pin "1") (pinfunction "1_1") (pintype "input"))
      (node (ref "R3") (pin "1") (pinfunction "1_1") (pintype "input"))
      (node (ref "R5") (pin "2") (pinfunction "2_2") (pintype "input"))
      (node (ref "SW1") (pin "2") (pinfunction "2_2") (pintype "input"))
      (node (ref "U3") (pin "1") (pinfunction "TEMP_1") (pintype "input"))
      (node (ref "U3") (pin "3") (pinfunction "GND_3") (pintype "input"))
      (node (ref "U3") (pin "9") (pinfunction "EP_9") (pintype "input"))
      (node (ref "U4") (pin "23") (pinfunction "VSS_23") (pintype "input"))
      (node (ref "U4") (pin "35") (pinfunction "VSS_35") (pintype "input"))
      (node (ref "U4") (pin "47") (pinfunction "VSS_47") (pintype "input"))
      (node (ref "U4") (pin "49") (pinfunction "EP_49") (pintype "input"))
      (node (ref "U4") (pin "8") (pinfunction "VSSAVREF-_8") (pintype "input"))
      (node (ref "U7") (pin "1") (pinfunction "1_1") (pintype "input"))
      (node (ref "U7") (pin "3") (pinfunction "3_3") (pintype "input"))
      (node (ref "U7") (pin "4") (pinfunction "4_4") (pintype "input"))
      (node (ref "U8") (pin "4") (pinfunction "4_4") (pintype "input"))
      (node (ref "U8") (pin "5") (pinfunction "5_5") (pintype "input"))
      (node (ref "U8") (pin "6") (pinfunction "6_6") (pintype "input"))
      (node (ref "U9") (pin "13") (pinfunction "PS/SYNC_13") (pintype "input"))
      (node (ref "U9") (pin "15") (pinfunction "PGND_15") (pintype "input"))
      (node (ref "U9") (pin "2") (pinfunction "GND_2") (pintype "input"))
      (node (ref "USB2") (pin "A1B12") (pinfunction "GND_A1B12") (pintype "input"))
      (node (ref "USB2") (pin "B1A12") (pinfunction "GND_B1A12") (pintype "input"))
      (node (ref "USB2") (pin "EP") (pinfunction "EP_EP") (pintype "input"))
      (node (ref "X1") (pin "2") (pinfunction "GND_2") (pintype "input"))
      (node (ref "X1") (pin "4") (pinfunction "GND_4") (pintype "input"))
    )
    (net (code "41") (name "Net-(L1-Pad1)") (class "Default")
      (node (ref "L1") (pin "1") (pinfunction "1_1") (pintype "input"))
      (node (ref "U9") (pin "8") (pinfunction "L1_8") (pintype "input"))
      (node (ref "U9") (pin "9") (pinfunction "L1_9") (pintype "input"))
    )
    (net (code "42") (name "Net-(L1-Pad2)") (class "Default")
      (node (ref "L1") (pin "2") (pinfunction "2_2") (pintype "input"))
      (node (ref "U9") (pin "6") (pinfunction "L2_6") (pintype "input"))
      (node (ref "U9") (pin "7") (pinfunction "L2_7") (pintype "input"))
    )
    (net (code "43") (name "Net-(LED1-A)") (class "Default")
      (node (ref "LED1") (pin "1") (pinfunction "A_1") (pintype "input"))
      (node (ref "R11") (pin "1") (pinfunction "1_1") (pintype "input"))
    )
    (net (code "44") (name "Net-(LED2-A)") (class "Default")
      (node (ref "LED2") (pin "1") (pinfunction "A_1") (pintype "input"))
      (node (ref "R13") (pin "1") (pinfunction "1_1") (pintype "input"))
    )
    (net (code "45") (name "Net-(Q1-G)") (class "Default")
      (node (ref "Q1") (pin "2") (pinfunction "G_2") (pintype "input"))
      (node (ref "Q3") (pin "3") (pinfunction "C_3") (pintype "input"))
      (node (ref "R7") (pin "1") (pinfunction "1_1") (pintype "input"))
    )
    (net (code "46") (name "Net-(Q3-B)") (class "Default")
      (node (ref "Q3") (pin "1") (pinfunction "B_1") (pintype "input"))
      (node (ref "R6") (pin "2") (pinfunction "2_2") (pintype "input"))
    )
    (net (code "47") (name "Net-(R4-Pad2)") (class "Default")
      (node (ref "R4") (pin "2") (pinfunction "2_2") (pintype "input"))
      (node (ref "SW2") (pin "1") (pinfunction "1_1") (pintype "input"))
    )
    (net (code "48") (name "Net-(U3-FB)") (class "Default")
      (node (ref "R14") (pin "1") (pinfunction "1_1") (pintype "unspecified"))
      (node (ref "U3") (pin "8") (pinfunction "FB_8") (pintype "input"))
    )
    (net (code "49") (name "Net-(U3-ISET)") (class "Default")
      (node (ref "R12") (pin "2") (pinfunction "2_2") (pintype "input"))
      (node (ref "U3") (pin "2") (pinfunction "ISET_2") (pintype "input"))
    )
    (net (code "50") (name "Net-(U4-BOOT0)") (class "Default")
      (node (ref "R4") (pin "1") (pinfunction "1_1") (pintype "input"))
      (node (ref "R5") (pin "1") (pinfunction "1_1") (pintype "input"))
      (node (ref "U4") (pin "44") (pinfunction "BOOT0_44") (pintype "input"))
    )
    (net (code "51") (name "Net-(U4-NRST)") (class "Default")
      (node (ref "C6") (pin "2") (pinfunction "2_2") (pintype "input"))
      (node (ref "SW1") (pin "1") (pinfunction "1_1") (pintype "input"))
      (node (ref "U4") (pin "7") (pinfunction "NRST_7") (pintype "bidirectional"))
    )
    (net (code "52") (name "Net-(U4-PH0-OSC_IN)") (class "Default")
      (node (ref "C9") (pin "2") (pinfunction "2_2") (pintype "input"))
      (node (ref "U4") (pin "5") (pinfunction "PH0-OSC_IN_5") (pintype "bidirectional"))
      (node (ref "X1") (pin "1") (pinfunction "OSC1_1") (pintype "input"))
    )
    (net (code "53") (name "Net-(U4-PH1-OSC_OUT)") (class "Default")
      (node (ref "C10") (pin "2") (pinfunction "2_2") (pintype "input"))
      (node (ref "U4") (pin "6") (pinfunction "PH1-OSC_OUT_6") (pintype "bidirectional"))
      (node (ref "X1") (pin "3") (pinfunction "OSC2_3") (pintype "input"))
    )
    (net (code "54") (name "Net-(U4-VCAP1)") (class "Default")
      (node (ref "C5") (pin "2") (pinfunction "2_2") (pintype "input"))
      (node (ref "U4") (pin "22") (pinfunction "VCAP1_22") (pintype "input"))
    )
    (net (code "55") (name "Net-(U4-VDDAVREF+)") (class "Default")
      (node (ref "C7") (pin "2") (pinfunction "2_2") (pintype "input"))
      (node (ref "C8") (pin "2") (pinfunction "2_2") (pintype "input"))
      (node (ref "R17") (pin "1") (pinfunction "1_1") (pintype "input"))
      (node (ref "U4") (pin "9") (pinfunction "VDDAVREF+_9") (pintype "input"))
    )
    (net (code "56") (name "Net-(U9-FB)") (class "Default")
      (node (ref "R10") (pin "2") (pinfunction "2_2") (pintype "input"))
      (node (ref "R9") (pin "1") (pinfunction "1_1") (pintype "input"))
      (node (ref "U9") (pin "3") (pinfunction "FB_3") (pintype "input"))
    )
    (net (code "57") (name "unconnected-(U3-DONE#-Pad6)") (class "Default")
      (node (ref "U3") (pin "6") (pinfunction "DONE#_6") (pintype "input+no_connect"))
    )
    (net (code "58") (name "unconnected-(U9-PG-Pad14)") (class "Default")
      (node (ref "U9") (pin "14") (pinfunction "PG_14") (pintype "input+no_connect"))
    )
    (net (code "59") (name "unconnected-(USB2-CC1-PadA5)") (class "Default")
      (node (ref "USB2") (pin "A5") (pinfunction "CC1_A5") (pintype "input+no_connect"))
    )
    (net (code "60") (name "unconnected-(USB2-CC2-PadB5)") (class "Default")
      (node (ref "USB2") (pin "B5") (pinfunction "CC2_B5") (pintype "input+no_connect"))
    )
    (net (code "61") (name "unconnected-(USB2-SBU1-PadA8)") (class "Default")
      (node (ref "USB2") (pin "A8") (pinfunction "SBU1_A8") (pintype "input+no_connect"))
    )
    (net (code "62") (name "unconnected-(USB2-SBU2-PadB8)") (class "Default")
      (node (ref "USB2") (pin "B8") (pinfunction "SBU2_B8") (pintype "input+no_connect"))
    )
  )
)
